# canada150.net
KiCad netlist of a schematic drawn in EAGLE
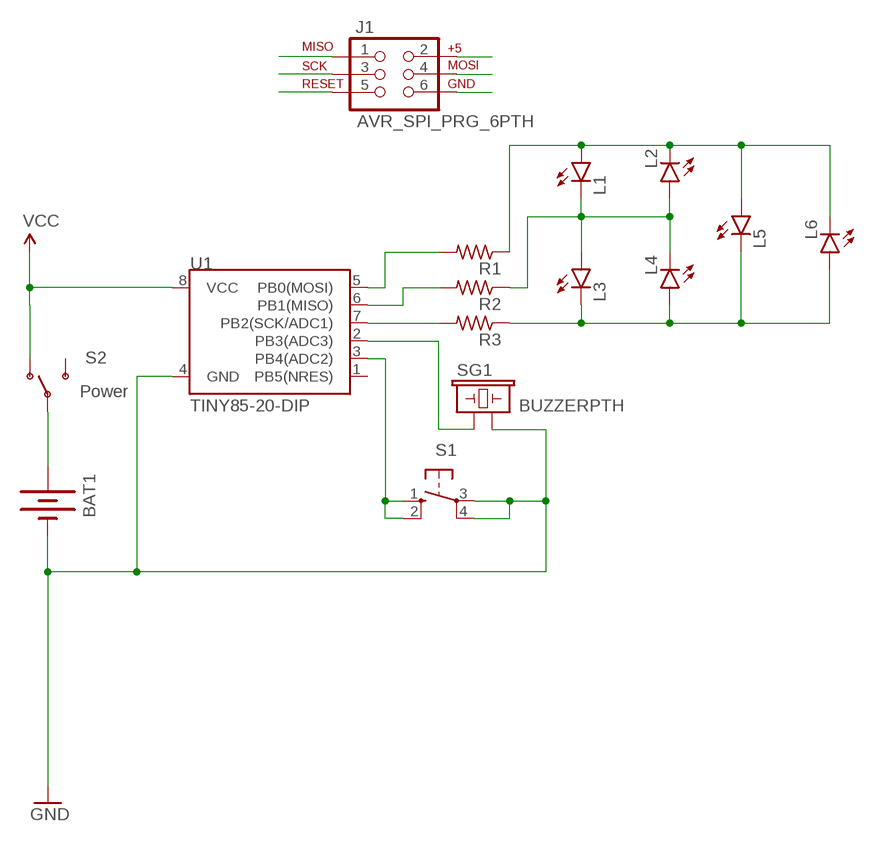
[diagram p0: schematic, sheet 1]

(export (version "E")
  (design (tool "Eeschema 10.0.6"))
  (components
    (comp (ref "BAT1")
      (value "BATTERY20PTH")
      (footprint "eagle-import:BATTCOM_20MM_PTH")
      (libsource (lib "eagle-import") (part "BATTERY20PTH"))
    )
    (comp (ref "J1")
      (value "AVR_SPI_PRG_6PTH")
      (footprint "eagle-import:2X3")
      (libsource (lib "eagle-import") (part "AVR_SPI_PRG_6PTH"))
    )
    (comp (ref "L1")
      (value "LED5MM")
      (footprint "eagle-import:LED5MM")
      (libsource (lib "eagle-import") (part "LED5MM"))
    )
    (comp (ref "L2")
      (value "LED5MM")
      (footprint "eagle-import:LED5MM")
      (libsource (lib "eagle-import") (part "LED5MM"))
    )
    (comp (ref "L3")
      (value "LED5MM")
      (footprint "eagle-import:LED5MM")
      (libsource (lib "eagle-import") (part "LED5MM"))
    )
    (comp (ref "L4")
      (value "LED5MM")
      (footprint "eagle-import:LED5MM")
      (libsource (lib "eagle-import") (part "LED5MM"))
    )
    (comp (ref "L5")
      (value "LED5MM")
      (footprint "eagle-import:LED5MM")
      (libsource (lib "eagle-import") (part "LED5MM"))
    )
    (comp (ref "L6")
      (value "LED5MM")
      (footprint "eagle-import:LED5MM")
      (libsource (lib "eagle-import") (part "LED5MM"))
    )
    (comp (ref "R1")
      (value "R-US_0204/7")
      (footprint "eagle-import:0204_7")
      (libsource (lib "eagle-import") (part "R-US_0204/7"))
    )
    (comp (ref "R2")
      (value "R-US_0204/7")
      (footprint "eagle-import:0204_7")
      (libsource (lib "eagle-import") (part "R-US_0204/7"))
    )
    (comp (ref "R3")
      (value "R-US_0204/7")
      (footprint "eagle-import:0204_7")
      (libsource (lib "eagle-import") (part "R-US_0204/7"))
    )
    (comp (ref "S1")
      (value "10-XX")
      (footprint "eagle-import:B3F-10XX")
      (fields (field (name "MPN") "B3F-1000"))
      (libsource (lib "eagle-import") (part "10-XX"))
    )
    (comp (ref "S2")
      (value "Power")
      (footprint "eagle-import:SWITCH-SPDT")
      (libsource (lib "eagle-import") (part "SWITCH-SPDTPTH"))
    )
    (comp (ref "SG1")
      (value "BUZZERPTH")
      (footprint "eagle-import:BUZZER-12MM")
      (libsource (lib "eagle-import") (part "BUZZERPTH"))
    )
    (comp (ref "U1")
      (value "TINY85-20-DIP")
      (footprint "eagle-import:DIP08")
      (libsource (lib "eagle-import") (part "ATTINY45TINY85-20-DIP"))
    )
  )
  (nets
    (net (code "1") (name "/MISO") (class "Default")
      (node (ref "J1") (pin "1") (pinfunction "1_1") (pintype "passive"))
      (node (ref "R2") (pin "2") (pinfunction "2_2") (pintype "passive"))
      (node (ref "U1") (pin "6") (pinfunction "PB1(MISO)_6") (pintype "bidirectional"))
    )
    (net (code "2") (name "/MOSI") (class "Default")
      (node (ref "J1") (pin "4") (pinfunction "4_4") (pintype "passive"))
      (node (ref "R1") (pin "2") (pinfunction "2_2") (pintype "passive"))
      (node (ref "U1") (pin "5") (pinfunction "PB0(MOSI)_5") (pintype "bidirectional"))
    )
    (net (code "3") (name "/SCK") (class "Default")
      (node (ref "J1") (pin "3") (pinfunction "3_3") (pintype "passive"))
      (node (ref "R3") (pin "2") (pinfunction "2_2") (pintype "passive"))
      (node (ref "U1") (pin "7") (pinfunction "PB2(SCK/ADC1)_7") (pintype "bidirectional"))
    )
    (net (code "4") (name "GND") (class "Default")
      (node (ref "BAT1") (pin "2") (pinfunction "-_2") (pintype "power_in"))
      (node (ref "J1") (pin "6") (pinfunction "6_6") (pintype "passive"))
      (node (ref "S1") (pin "3") (pinfunction "P_3") (pintype "passive"))
      (node (ref "S1") (pin "4") (pinfunction "P1_4") (pintype "passive"))
      (node (ref "SG1") (pin "-") (pinfunction "2_-") (pintype "passive"))
      (node (ref "U1") (pin "4") (pinfunction "GND_4") (pintype "bidirectional"))
    )
    (net (code "5") (name "Net-(BAT1-+)") (class "Default")
      (node (ref "BAT1") (pin "1") (pinfunction "+_1") (pintype "power_in"))
      (node (ref "S2") (pin "2") (pinfunction "P_2") (pintype "passive"))
    )
    (net (code "6") (name "Net-(L1-C)") (class "Default")
      (node (ref "L1") (pin "K") (pinfunction "C_K") (pintype "passive"))
      (node (ref "L2") (pin "A") (pinfunction "A_A") (pintype "passive"))
      (node (ref "L3") (pin "A") (pinfunction "A_A") (pintype "passive"))
      (node (ref "L4") (pin "K") (pinfunction "C_K") (pintype "passive"))
      (node (ref "R2") (pin "1") (pinfunction "1_1") (pintype "passive"))
    )
    (net (code "7") (name "Net-(L2-C)") (class "Default")
      (node (ref "L1") (pin "A") (pinfunction "A_A") (pintype "passive"))
      (node (ref "L2") (pin "K") (pinfunction "C_K") (pintype "passive"))
      (node (ref "L5") (pin "A") (pinfunction "A_A") (pintype "passive"))
      (node (ref "L6") (pin "K") (pinfunction "C_K") (pintype "passive"))
      (node (ref "R1") (pin "1") (pinfunction "1_1") (pintype "passive"))
    )
    (net (code "8") (name "Net-(L3-C)") (class "Default")
      (node (ref "L3") (pin "K") (pinfunction "C_K") (pintype "passive"))
      (node (ref "L4") (pin "A") (pinfunction "A_A") (pintype "passive"))
      (node (ref "L5") (pin "K") (pinfunction "C_K") (pintype "passive"))
      (node (ref "L6") (pin "A") (pinfunction "A_A") (pintype "passive"))
      (node (ref "R3") (pin "1") (pinfunction "1_1") (pintype "passive"))
    )
    (net (code "9") (name "Net-(S1-S)") (class "Default")
      (node (ref "S1") (pin "1") (pinfunction "S_1") (pintype "passive"))
      (node (ref "S1") (pin "2") (pinfunction "S1_2") (pintype "passive"))
      (node (ref "U1") (pin "3") (pinfunction "PB4(ADC2)_3") (pintype "bidirectional"))
    )
    (net (code "10") (name "Net-(SG1-1)") (class "Default")
      (node (ref "SG1") (pin "+") (pinfunction "1_+") (pintype "passive"))
      (node (ref "U1") (pin "2") (pinfunction "PB3(ADC3)_2") (pintype "bidirectional"))
    )
    (net (code "11") (name "VCC") (class "Default")
      (node (ref "J1") (pin "2") (pinfunction "2_2") (pintype "passive"))
      (node (ref "S2") (pin "1") (pinfunction "O_1") (pintype "passive"))
      (node (ref "U1") (pin "8") (pinfunction "VCC_8") (pintype "bidirectional"))
    )
    (net (code "12") (name "unconnected-(J1-Pad5)") (class "Default")
      (node (ref "J1") (pin "5") (pinfunction "5_5") (pintype "passive"))
    )
    (net (code "13") (name "unconnected-(S2-S-Pad3)") (class "Default")
      (node (ref "S2") (pin "3") (pinfunction "S_3") (pintype "passive"))
    )
    (net (code "14") (name "unconnected-(U1-PB5(NRES)-Pad1)") (class "Default")
      (node (ref "U1") (pin "1") (pinfunction "PB5(NRES)_1") (pintype "bidirectional"))
    )
  )
)
